# PortaPill_MainBoard.net
KiCad netlist of a schematic drawn in Altium Designer
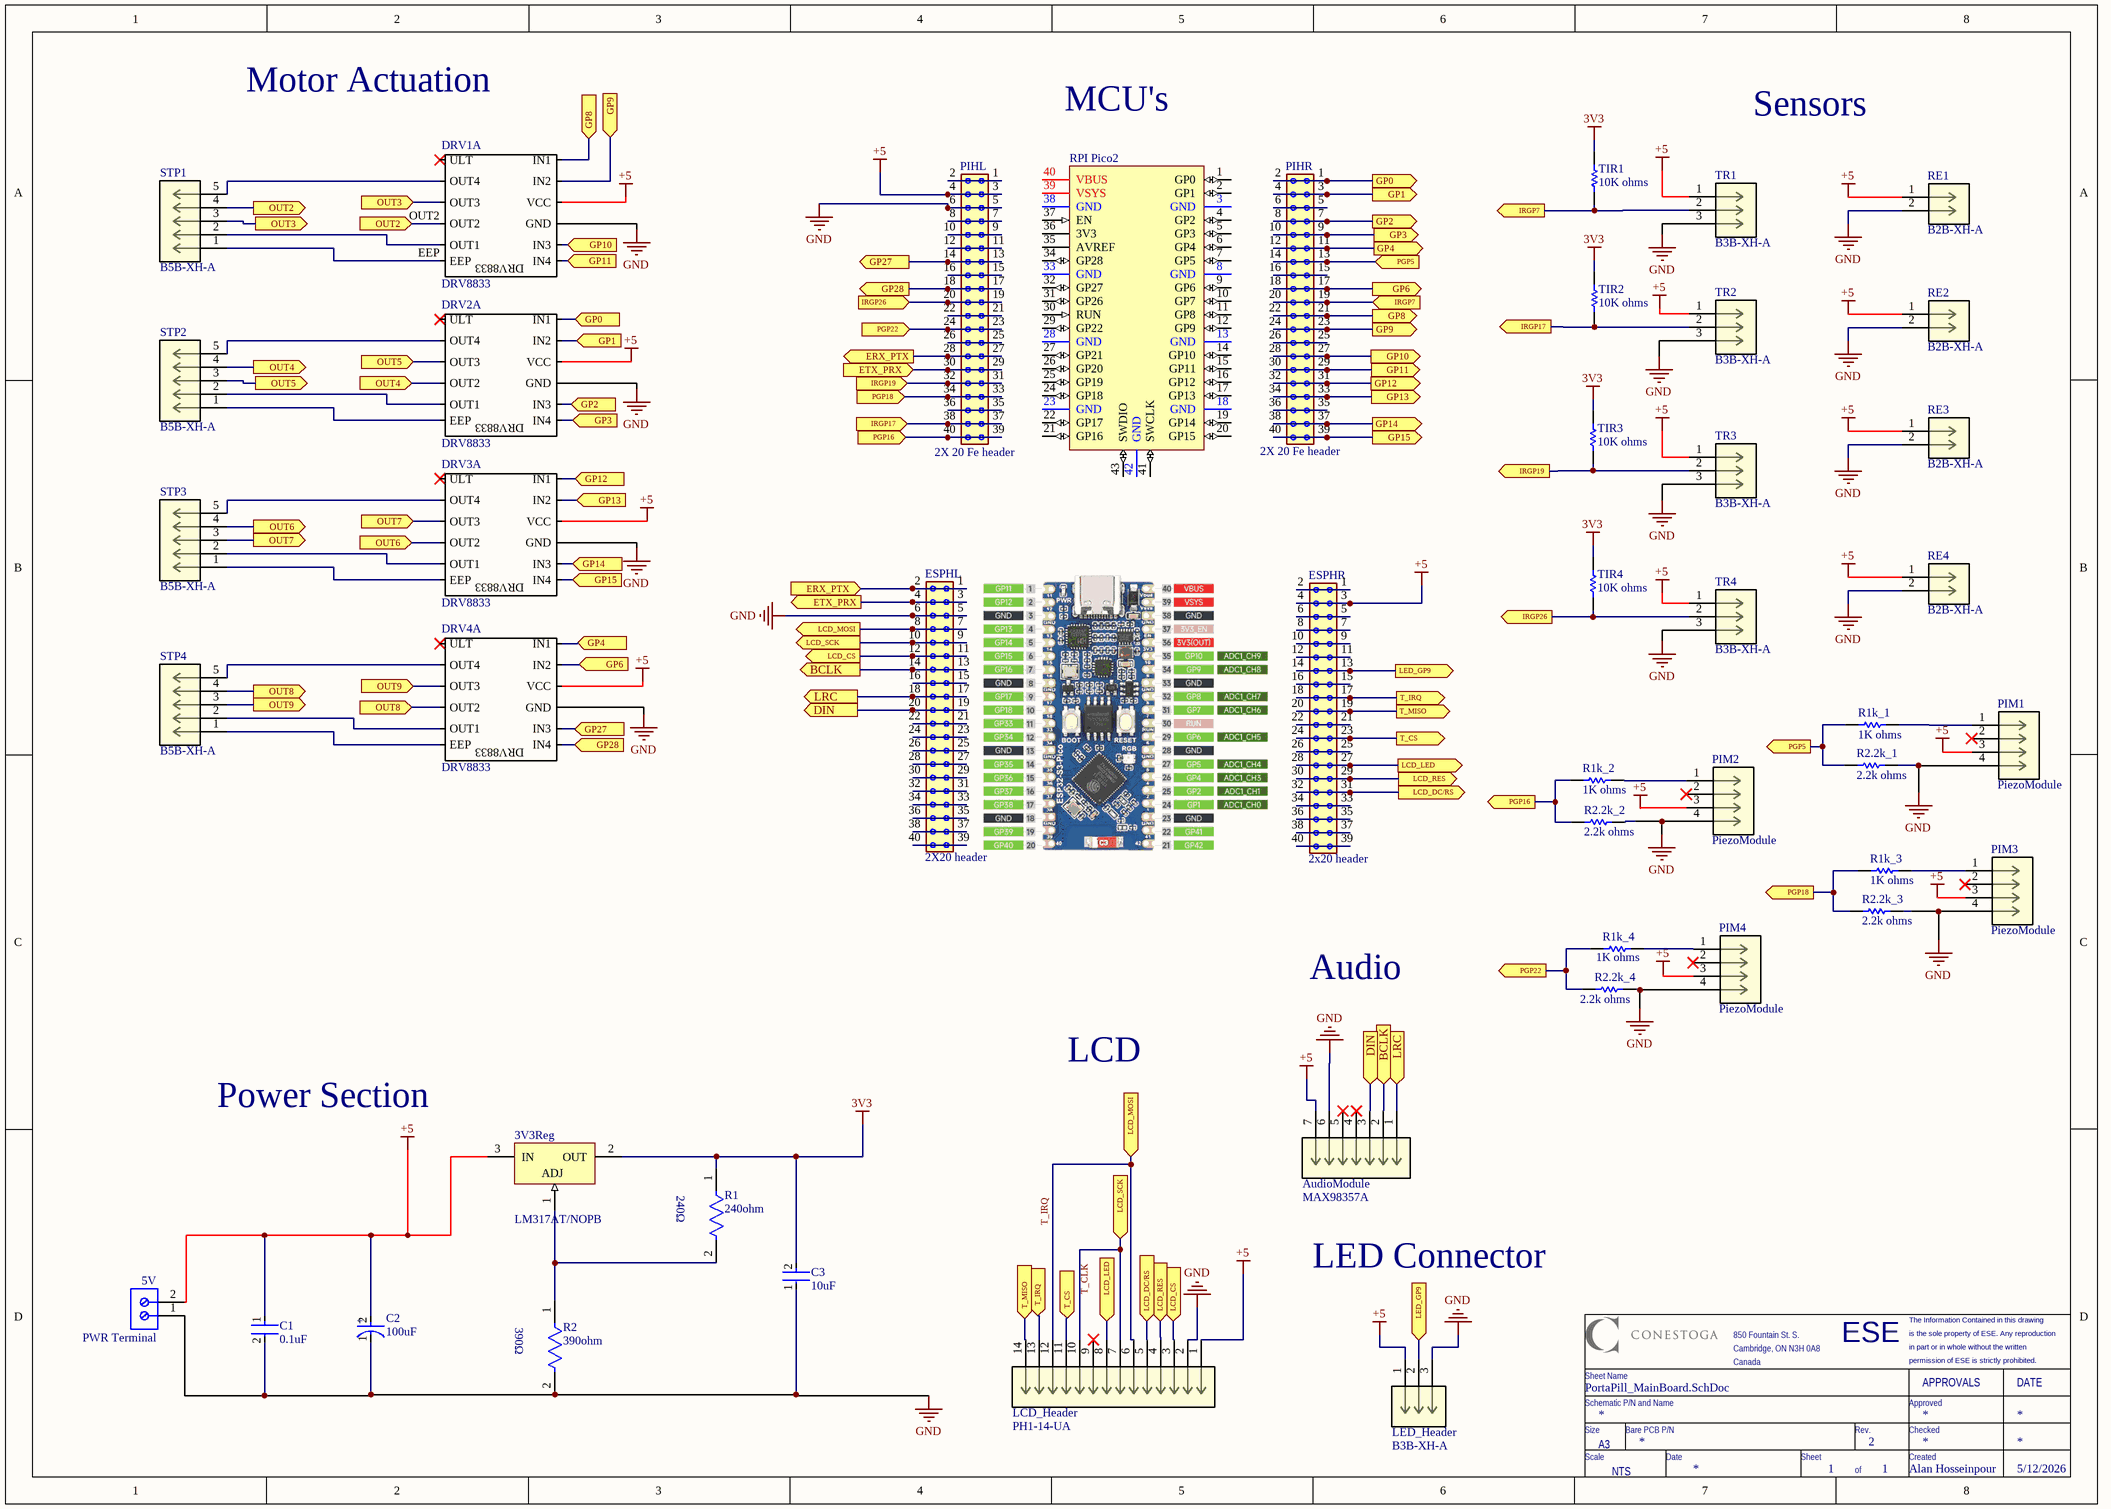
[diagram p0: PortaPill_MainBoard.SchDoc]

(export (version "E")
  (design (tool "Eeschema 10.0.6"))
  (components
    (comp (ref "3V3Reg")
      (value "LM317AT/NOPB")
      (footprint "NDE0003A")
      (description "3-Terminal Adjustable Regulator, 3-pin TO-220, Pb-Free")
      (fields (field (name "MANUFACTURER") "Texas Instruments"))
      (libsource (lib "Altium Content Vault") (part "PM-REG-LM1086ADJ-SIL3"))
    )
    (comp (ref "AudioModule")
      (value "MAX98357A")
      (footprint "CONN07_901471107_MOL")
      (description "C-Grid III PC Board Connector, Single Row, Vertical, 7 Circuits, Tin (Sn) Plating")
      (fields
        (field (name "MANUFACTURER_PART_NUMBER") "901471107")
        (field (name "COPYRIGHT") "Copyright (C) 2026 Ultra Librarian. All rights reserved.")
      )
      (libsource (lib "901471107") (part "901471107"))
    )
    (comp (ref "C1")
      (value "0.1uF")
      (footprint "FP-C410C104M5U5TA7200-MFG")
      (description "C410C104M5U5TA7200\r\nCAP CER 0.1UF 50V Z5U AXIAL")
      (fields (field (name "TOLERANCE") "20%"))
      (libsource (lib "Altium Content Vault") (part "b4654b650e69147ec39a6b967a45e02"))
    )
    (comp (ref "C2")
      (value "100uF")
      (footprint "FP-RAD-TH-D_12_5_0_5-L_25-MFG")
      (description "Aluminum Electrolytic Capacitors (Radial Lead Type) 100uF ±20% 160V\r\nEEUED2C101")
      (fields (field (name "VOLTAGE") "160V") (field (name "TOLERANCE") "20%"))
      (libsource (lib "Altium Content Vault") (part "203bc49f2ac43e59fd269a8c329ed05"))
    )
    (comp (ref "C3")
      (value "10uF")
      (footprint "FP-DE2_D15_T5_F7_5_d0_6-0-MFG")
      (description "Cap Ceramic Disc 10000pF 20% 250VAC Thru-Hole 15.0x5.0x7.5 Bulk\r\n\r\nDE2E3SA103MJ3BT02F")
      (libsource (lib "Altium Content Vault") (part "236180d848d6139a670b325ea6854c9"))
    )
    (comp (ref "DRV1")
      (value "DRV8833")
      (footprint "DRV8833")
      (description "Motor Driver")
      (libsource (lib "") (part "DRV8833_1"))
    )
    (comp (ref "DRV2")
      (value "DRV8833")
      (footprint "DRV8833")
      (description "Motor Driver")
      (libsource (lib "Capstone I library") (part "DRV8833"))
    )
    (comp (ref "DRV3")
      (value "DRV8833")
      (footprint "DRV8833")
      (description "Motor Driver")
      (libsource (lib "Capstone I library") (part "DRV8833"))
    )
    (comp (ref "DRV4")
      (value "DRV8833")
      (footprint "DRV8833")
      (description "Motor Driver")
      (libsource (lib "Capstone I library") (part "DRV8833"))
    )
    (comp (ref "ESPHL")
      (value "2X20 header")
      (footprint "61304021821")
      (description "40 Position Receptacle Connector 0.100 (2.54mm) Through Hole Gold")
      (fields (field (name "MF") "WÃ¼rth Elektronik") (field (name "MP") "61304021821"))
      (libsource (lib "6130XX21821_61304021821") (part "6130XX21821_61304021821"))
    )
    (comp (ref "ESPHR")
      (value "2x20 header")
      (footprint "61304021821")
      (description "40 Position Receptacle Connector 0.100 (2.54mm) Through Hole Gold")
      (fields (field (name "MF") "WÃ¼rth Elektronik") (field (name "MP") "61304021821"))
      (libsource (lib "6130XX21821_61304021821") (part "6130XX21821_61304021821"))
    )
    (comp (ref "LCD_Header")
      (value "PH1-14-UA")
      (footprint "CONN_PH1-14-UA_ADM")
      (description "Description")
      (fields (field (name "COPYRIGHT") "Copyright (C) 2025 Ultra Librarian. All rights reserved."))
      (libsource (lib "PH1-14-UA") (part "PH1-14-UA"))
    )
    (comp (ref "LED_Header")
      (value "B3B-XH-A")
      (footprint "CONN_B3B-XH-A_JST")
      (description "Description")
      (fields (field (name "COPYRIGHT") "Copyright (C) 2026 Ultra Librarian. All rights reserved."))
      (libsource (lib "") (part "B3B-XH-A_1"))
    )
    (comp (ref "PIHL")
      (value "2X 20 Fe header")
      (footprint "61304021821")
      (description "40 Position Receptacle Connector 0.100 (2.54mm) Through Hole Gold")
      (fields (field (name "MF") "WÃ¼rth Elektronik") (field (name "MP") "61304021821"))
      (libsource (lib "6130XX21821_61304021821") (part "6130XX21821_61304021821"))
    )
    (comp (ref "PIHR")
      (value "2X 20 Fe header")
      (footprint "61304021821")
      (description "40 Position Receptacle Connector 0.100 (2.54mm) Through Hole Gold")
      (fields (field (name "MF") "WÃ¼rth Elektronik") (field (name "MP") "61304021821"))
      (libsource (lib "6130XX21821_61304021821") (part "6130XX21821_61304021821"))
    )
    (comp (ref "PIM1")
      (value "PiezoModule")
      (footprint "CONN_PPTC041LFBN-RC_SUL")
      (description "Description")
      (fields
        (field (name "MANUFACTURER_PART_NUMBER") "PPTC041LFBN-RC")
        (field (name "COPYRIGHT") "Copyright (C) 2026 Ultra Librarian. All rights reserved.")
      )
      (libsource (lib "PPTC041LFBN-RC") (part "PPTC041LFBN-RC"))
    )
    (comp (ref "PIM2")
      (value "PiezoModule")
      (footprint "CONN_PPTC041LFBN-RC_SUL")
      (description "Description")
      (fields
        (field (name "MANUFACTURER_PART_NUMBER") "PPTC041LFBN-RC")
        (field (name "COPYRIGHT") "Copyright (C) 2026 Ultra Librarian. All rights reserved.")
      )
      (libsource (lib "PPTC041LFBN-RC") (part "PPTC041LFBN-RC"))
    )
    (comp (ref "PIM3")
      (value "PiezoModule")
      (footprint "CONN_PPTC041LFBN-RC_SUL")
      (description "Description")
      (fields
        (field (name "MANUFACTURER_PART_NUMBER") "PPTC041LFBN-RC")
        (field (name "COPYRIGHT") "Copyright (C) 2026 Ultra Librarian. All rights reserved.")
      )
      (libsource (lib "PPTC041LFBN-RC") (part "PPTC041LFBN-RC"))
    )
    (comp (ref "PIM4")
      (value "PiezoModule")
      (footprint "CONN_PPTC041LFBN-RC_SUL")
      (description "Description")
      (fields
        (field (name "MANUFACTURER_PART_NUMBER") "PPTC041LFBN-RC")
        (field (name "COPYRIGHT") "Copyright (C) 2026 Ultra Librarian. All rights reserved.")
      )
      (libsource (lib "PPTC041LFBN-RC") (part "PPTC041LFBN-RC"))
    )
    (comp (ref "PWR Terminal")
      (value "5V")
      (footprint "691216400002")
      (description "Terminal Block, Wtb, 2Way, 30-12Awg Rohs Compliant: Yes")
      (libsource (lib "Altium Content Vault") (part "TBL - 1R - 02P - Screw"))
    )
    (comp (ref "R1")
      (value "240ohm")
      (footprint "RR02_MFG")
      (description "Fixed Resistor, Metal Film, 2W, 240ohm, 500V, 5% +/-Tol, 300ppm/Cel, Through Hole Mount")
      (fields (field (name "TOLERANCE") "5%"))
      (libsource (lib "Altium Content Vault") (part "beb0a2e81d78bb8429d162089e89c6a"))
    )
    (comp (ref "R1k_1")
      (value "1K ohms")
      (footprint "RESA60-630X240")
      (description "Axial Resistor, 1 KOhm, +/- 1%, 250 mW, -55 to 155 degC, 2-Pin THD, RoHS, Bulk")
      (fields (field (name "TOLERANCE") "1%"))
      (libsource (lib "Altium Content Vault") (part "RES-2"))
    )
    (comp (ref "R1k_2")
      (value "1K ohms")
      (footprint "RESA60-630X240")
      (description "Axial Resistor, 1 KOhm, +/- 1%, 250 mW, -55 to 155 degC, 2-Pin THD, RoHS, Bulk")
      (fields (field (name "TOLERANCE") "1%"))
      (libsource (lib "Altium Content Vault") (part "RES-2"))
    )
    (comp (ref "R1k_3")
      (value "1K ohms")
      (footprint "RESA60-630X240")
      (description "Axial Resistor, 1 KOhm, +/- 1%, 250 mW, -55 to 155 degC, 2-Pin THD, RoHS, Bulk")
      (fields (field (name "TOLERANCE") "1%"))
      (libsource (lib "Altium Content Vault") (part "RES-2"))
    )
    (comp (ref "R1k_4")
      (value "1K ohms")
      (footprint "RESA60-630X240")
      (description "Axial Resistor, 1 KOhm, +/- 1%, 250 mW, -55 to 155 degC, 2-Pin THD, RoHS, Bulk")
      (fields (field (name "TOLERANCE") "1%"))
      (libsource (lib "Altium Content Vault") (part "RES-2"))
    )
    (comp (ref "R2")
      (value "390ohm")
      (footprint "RR02_MFG")
      (description "Fixed Resistor, Metal Film, 2W, 240ohm, 500V, 5% +/-Tol, 300ppm/Cel, Through Hole Mount")
      (fields (field (name "TOLERANCE") "5%"))
      (libsource (lib "Altium Content Vault") (part "beb0a2e81d78bb8429d162089e89c6a"))
    )
    (comp (ref "R2.2k_1")
      (value "2.2k ohms")
      (footprint "RESA60-630X240")
      (description "Axial Resistor, 1 KOhm, +/- 1%, 250 mW, -55 to 155 degC, 2-Pin THD, RoHS, Bulk")
      (fields (field (name "TOLERANCE") "1%"))
      (libsource (lib "Altium Content Vault") (part "RES-2"))
    )
    (comp (ref "R2.2k_2")
      (value "2.2k ohms")
      (footprint "RESA60-630X240")
      (description "Axial Resistor, 1 KOhm, +/- 1%, 250 mW, -55 to 155 degC, 2-Pin THD, RoHS, Bulk")
      (fields (field (name "TOLERANCE") "1%"))
      (libsource (lib "Altium Content Vault") (part "RES-2"))
    )
    (comp (ref "R2.2k_3")
      (value "2.2k ohms")
      (footprint "RESA60-630X240")
      (description "Axial Resistor, 1 KOhm, +/- 1%, 250 mW, -55 to 155 degC, 2-Pin THD, RoHS, Bulk")
      (fields (field (name "TOLERANCE") "1%"))
      (libsource (lib "Altium Content Vault") (part "RES-2"))
    )
    (comp (ref "R2.2k_4")
      (value "2.2k ohms")
      (footprint "RESA60-630X240")
      (description "Axial Resistor, 1 KOhm, +/- 1%, 250 mW, -55 to 155 degC, 2-Pin THD, RoHS, Bulk")
      (fields (field (name "TOLERANCE") "1%"))
      (libsource (lib "Altium Content Vault") (part "RES-2"))
    )
    (comp (ref "RE1")
      (value "B2B-XH-A")
      (footprint "CONN_B2B-XH-A_JST")
      (description "Description")
      (fields (field (name "COPYRIGHT") "Copyright (C) 2026 Ultra Librarian. All rights reserved."))
      (libsource (lib "B2B-XH-A") (part "B2B-XH-A"))
    )
    (comp (ref "RE2")
      (value "B2B-XH-A")
      (footprint "CONN_B2B-XH-A_JST")
      (description "Description")
      (fields (field (name "COPYRIGHT") "Copyright (C) 2026 Ultra Librarian. All rights reserved."))
      (libsource (lib "B2B-XH-A") (part "B2B-XH-A"))
    )
    (comp (ref "RE3")
      (value "B2B-XH-A")
      (footprint "CONN_B2B-XH-A_JST")
      (description "Description")
      (fields (field (name "COPYRIGHT") "Copyright (C) 2026 Ultra Librarian. All rights reserved."))
      (libsource (lib "B2B-XH-A") (part "B2B-XH-A"))
    )
    (comp (ref "RE4")
      (value "B2B-XH-A")
      (footprint "CONN_B2B-XH-A_JST")
      (description "Description")
      (fields (field (name "COPYRIGHT") "Copyright (C) 2026 Ultra Librarian. All rights reserved."))
      (libsource (lib "B2B-XH-A") (part "B2B-XH-A"))
    )
    (comp (ref "RPI Pico2")
      (value "RPI-PICO-MOD_SM")
      (footprint "AG.Modules:RPI-PICO-MOD")
      (description "RASPBERRY PI PICO RP2040 BOARD NO TEST PADS")
      (fields
        (field (name "MANUFACTURER") "Raspberry Pi Foundation")
        (field (name "MANUFACTURER PART NO") "SC0915")
      )
      (libsource (lib "RPi_Pico") (part "RPI-PICO-MOD_SM"))
    )
    (comp (ref "STP1")
      (value "B5B-XH-A")
      (footprint "CONN_B5B-XH-A_JST")
      (description "Description")
      (fields (field (name "COPYRIGHT") "Copyright (C) 2026 Ultra Librarian. All rights reserved."))
      (libsource (lib "B5B-XH-A") (part "B5B-XH-A"))
    )
    (comp (ref "STP2")
      (value "B5B-XH-A")
      (footprint "CONN_B5B-XH-A_JST")
      (description "Description")
      (fields (field (name "COPYRIGHT") "Copyright (C) 2026 Ultra Librarian. All rights reserved."))
      (libsource (lib "B5B-XH-A") (part "B5B-XH-A"))
    )
    (comp (ref "STP3")
      (value "B5B-XH-A")
      (footprint "CONN_B5B-XH-A_JST")
      (description "Description")
      (fields (field (name "COPYRIGHT") "Copyright (C) 2026 Ultra Librarian. All rights reserved."))
      (libsource (lib "B5B-XH-A") (part "B5B-XH-A"))
    )
    (comp (ref "STP4")
      (value "B5B-XH-A")
      (footprint "CONN_B5B-XH-A_JST")
      (description "Description")
      (fields (field (name "COPYRIGHT") "Copyright (C) 2026 Ultra Librarian. All rights reserved."))
      (libsource (lib "B5B-XH-A") (part "B5B-XH-A"))
    )
    (comp (ref "TIR1")
      (value "10K ohms")
      (footprint "RESA60-630X240")
      (description "Axial Resistor, 1 KOhm, +/- 1%, 250 mW, -55 to 155 degC, 2-Pin THD, RoHS, Bulk")
      (fields (field (name "TOLERANCE") "1%"))
      (libsource (lib "Altium Content Vault") (part "RES-2"))
    )
    (comp (ref "TIR2")
      (value "10K ohms")
      (footprint "RESA60-630X240")
      (description "Axial Resistor, 1 KOhm, +/- 1%, 250 mW, -55 to 155 degC, 2-Pin THD, RoHS, Bulk")
      (fields (field (name "TOLERANCE") "1%"))
      (libsource (lib "Altium Content Vault") (part "RES-2"))
    )
    (comp (ref "TIR3")
      (value "10K ohms")
      (footprint "RESA60-630X240")
      (description "Axial Resistor, 1 KOhm, +/- 1%, 250 mW, -55 to 155 degC, 2-Pin THD, RoHS, Bulk")
      (fields (field (name "TOLERANCE") "1%"))
      (libsource (lib "Altium Content Vault") (part "RES-2"))
    )
    (comp (ref "TIR4")
      (value "10K ohms")
      (footprint "RESA60-630X240")
      (description "Axial Resistor, 1 KOhm, +/- 1%, 250 mW, -55 to 155 degC, 2-Pin THD, RoHS, Bulk")
      (fields (field (name "TOLERANCE") "1%"))
      (libsource (lib "Altium Content Vault") (part "RES-2"))
    )
    (comp (ref "TR1")
      (value "B3B-XH-A")
      (footprint "CONN_B3B-XH-A_JST")
      (description "Description")
      (fields (field (name "COPYRIGHT") "Copyright (C) 2026 Ultra Librarian. All rights reserved."))
      (libsource (lib "B3B-XH-A") (part "B3B-XH-A"))
    )
    (comp (ref "TR2")
      (value "B3B-XH-A")
      (footprint "CONN_B3B-XH-A_JST")
      (description "Description")
      (fields (field (name "COPYRIGHT") "Copyright (C) 2026 Ultra Librarian. All rights reserved."))
      (libsource (lib "B3B-XH-A") (part "B3B-XH-A"))
    )
    (comp (ref "TR3")
      (value "B3B-XH-A")
      (footprint "CONN_B3B-XH-A_JST")
      (description "Description")
      (fields (field (name "COPYRIGHT") "Copyright (C) 2026 Ultra Librarian. All rights reserved."))
      (libsource (lib "B3B-XH-A") (part "B3B-XH-A"))
    )
    (comp (ref "TR4")
      (value "B3B-XH-A")
      (footprint "CONN_B3B-XH-A_JST")
      (description "Description")
      (fields (field (name "COPYRIGHT") "Copyright (C) 2026 Ultra Librarian. All rights reserved."))
      (libsource (lib "B3B-XH-A") (part "B3B-XH-A"))
    )
  )
  (nets
    (net (code "1") (name "+5") (class "Default")
      (node (ref "3V3Reg") (pin "3") (pinfunction "IN_3") (pintype "power_in"))
      (node (ref "AudioModule") (pin "7") (pinfunction "7_7") (pintype "passive"))
      (node (ref "C1") (pin "1") (pinfunction "1_1") (pintype "passive"))
      (node (ref "C2") (pin "2") (pinfunction "A_2") (pintype "passive"))
      (node (ref "DRV1") (pin "VCC") (pinfunction "VCC_VCC") (pintype "passive"))
      (node (ref "DRV2") (pin "VCC") (pinfunction "VCC_VCC") (pintype "passive"))
      (node (ref "DRV3") (pin "VCC") (pinfunction "VCC_VCC") (pintype "passive"))
      (node (ref "DRV4") (pin "VCC") (pinfunction "VCC_VCC") (pintype "passive"))
      (node (ref "ESPHR") (pin "3") (pinfunction "3_3") (pintype "passive"))
      (node (ref "ESPHR") (pin "4") (pinfunction "4_4") (pintype "passive"))
      (node (ref "LCD_Header") (pin "1") (pinfunction "1_1") (pintype "passive"))
      (node (ref "LED_Header") (pin "1") (pinfunction "1_1") (pintype "passive"))
      (node (ref "PIHL") (pin "3") (pinfunction "3_3") (pintype "passive"))
      (node (ref "PIHL") (pin "4") (pinfunction "4_4") (pintype "passive"))
      (node (ref "PIM1") (pin "3") (pinfunction "3_3") (pintype "passive"))
      (node (ref "PIM2") (pin "3") (pinfunction "3_3") (pintype "passive"))
      (node (ref "PIM3") (pin "3") (pinfunction "3_3") (pintype "passive"))
      (node (ref "PIM4") (pin "3") (pinfunction "3_3") (pintype "passive"))
      (node (ref "PWR Terminal") (pin "2") (pinfunction "2_2") (pintype "passive"))
      (node (ref "RE1") (pin "1") (pinfunction "1_1") (pintype "passive"))
      (node (ref "RE2") (pin "1") (pinfunction "1_1") (pintype "passive"))
      (node (ref "RE3") (pin "1") (pinfunction "1_1") (pintype "passive"))
      (node (ref "RE4") (pin "1") (pinfunction "1_1") (pintype "passive"))
      (node (ref "TR1") (pin "1") (pinfunction "1_1") (pintype "passive"))
      (node (ref "TR2") (pin "1") (pinfunction "1_1") (pintype "passive"))
      (node (ref "TR3") (pin "1") (pinfunction "1_1") (pintype "passive"))
      (node (ref "TR4") (pin "1") (pinfunction "1_1") (pintype "passive"))
    )
    (net (code "2") (name "/BCLK") (class "Default")
      (node (ref "AudioModule") (pin "2") (pinfunction "2_2") (pintype "passive"))
      (node (ref "ESPHL") (pin "13") (pinfunction "13_13") (pintype "passive"))
      (node (ref "ESPHL") (pin "14") (pinfunction "14_14") (pintype "passive"))
    )
    (net (code "3") (name "/DIN") (class "Default")
      (node (ref "AudioModule") (pin "3") (pinfunction "3_3") (pintype "passive"))
      (node (ref "ESPHL") (pin "19") (pinfunction "19_19") (pintype "passive"))
      (node (ref "ESPHL") (pin "20") (pinfunction "20_20") (pintype "passive"))
    )
    (net (code "4") (name "/ERX_PTX") (class "Default")
      (node (ref "ESPHL") (pin "1") (pinfunction "1_1") (pintype "passive"))
      (node (ref "ESPHL") (pin "2") (pinfunction "2_2") (pintype "passive"))
      (node (ref "PIHL") (pin "27") (pinfunction "27_27") (pintype "passive"))
      (node (ref "PIHL") (pin "28") (pinfunction "28_28") (pintype "passive"))
    )
    (net (code "5") (name "/ETX_PRX") (class "Default")
      (node (ref "ESPHL") (pin "3") (pinfunction "3_3") (pintype "passive"))
      (node (ref "ESPHL") (pin "4") (pinfunction "4_4") (pintype "passive"))
      (node (ref "PIHL") (pin "29") (pinfunction "29_29") (pintype "passive"))
      (node (ref "PIHL") (pin "30") (pinfunction "30_30") (pintype "passive"))
    )
    (net (code "6") (name "/GP0") (class "Default")
      (node (ref "DRV2") (pin "IN1") (pinfunction "IN1_IN1") (pintype "passive"))
      (node (ref "PIHR") (pin "1") (pinfunction "1_1") (pintype "passive"))
      (node (ref "PIHR") (pin "2") (pinfunction "2_2") (pintype "passive"))
    )
    (net (code "7") (name "/GP1") (class "Default")
      (node (ref "DRV2") (pin "IN2") (pinfunction "IN2_IN2") (pintype "passive"))
      (node (ref "PIHR") (pin "3") (pinfunction "3_3") (pintype "passive"))
      (node (ref "PIHR") (pin "4") (pinfunction "4_4") (pintype "passive"))
    )
    (net (code "8") (name "/GP2") (class "Default")
      (node (ref "DRV2") (pin "IN3") (pinfunction "IN3_IN3") (pintype "passive"))
      (node (ref "PIHR") (pin "7") (pinfunction "7_7") (pintype "passive"))
      (node (ref "PIHR") (pin "8") (pinfunction "8_8") (pintype "passive"))
    )
    (net (code "9") (name "/GP3") (class "Default")
      (node (ref "DRV2") (pin "IN4") (pinfunction "IN4_IN4") (pintype "passive"))
      (node (ref "PIHR") (pin "10") (pinfunction "10_10") (pintype "passive"))
      (node (ref "PIHR") (pin "9") (pinfunction "9_9") (pintype "passive"))
    )
    (net (code "10") (name "/GP4") (class "Default")
      (node (ref "DRV4") (pin "IN1") (pinfunction "IN1_IN1") (pintype "passive"))
      (node (ref "PIHR") (pin "11") (pinfunction "11_11") (pintype "passive"))
      (node (ref "PIHR") (pin "12") (pinfunction "12_12") (pintype "passive"))
    )
    (net (code "11") (name "/GP6") (class "Default")
      (node (ref "DRV4") (pin "IN2") (pinfunction "IN2_IN2") (pintype "passive"))
      (node (ref "PIHR") (pin "17") (pinfunction "17_17") (pintype "passive"))
      (node (ref "PIHR") (pin "18") (pinfunction "18_18") (pintype "passive"))
    )
    (net (code "12") (name "/GP8") (class "Default")
      (node (ref "DRV1") (pin "IN1") (pinfunction "IN1_IN1") (pintype "passive"))
      (node (ref "PIHR") (pin "21") (pinfunction "21_21") (pintype "passive"))
      (node (ref "PIHR") (pin "22") (pinfunction "22_22") (pintype "passive"))
    )
    (net (code "13") (name "/GP9") (class "Default")
      (node (ref "DRV1") (pin "IN2") (pinfunction "IN2_IN2") (pintype "passive"))
      (node (ref "PIHR") (pin "23") (pinfunction "23_23") (pintype "passive"))
      (node (ref "PIHR") (pin "24") (pinfunction "24_24") (pintype "passive"))
    )
    (net (code "14") (name "/GP10") (class "Default")
      (node (ref "DRV1") (pin "IN3") (pinfunction "IN3_IN3") (pintype "passive"))
      (node (ref "PIHR") (pin "27") (pinfunction "27_27") (pintype "passive"))
      (node (ref "PIHR") (pin "28") (pinfunction "28_28") (pintype "passive"))
    )
    (net (code "15") (name "/GP11") (class "Default")
      (node (ref "DRV1") (pin "IN4") (pinfunction "IN4_IN4") (pintype "passive"))
      (node (ref "PIHR") (pin "29") (pinfunction "29_29") (pintype "passive"))
      (node (ref "PIHR") (pin "30") (pinfunction "30_30") (pintype "passive"))
    )
    (net (code "16") (name "/GP12") (class "Default")
      (node (ref "DRV3") (pin "IN1") (pinfunction "IN1_IN1") (pintype "passive"))
      (node (ref "PIHR") (pin "31") (pinfunction "31_31") (pintype "passive"))
      (node (ref "PIHR") (pin "32") (pinfunction "32_32") (pintype "passive"))
    )
    (net (code "17") (name "/GP13") (class "Default")
      (node (ref "DRV3") (pin "IN2") (pinfunction "IN2_IN2") (pintype "passive"))
      (node (ref "PIHR") (pin "33") (pinfunction "33_33") (pintype "passive"))
      (node (ref "PIHR") (pin "34") (pinfunction "34_34") (pintype "passive"))
    )
    (net (code "18") (name "/GP14") (class "Default")
      (node (ref "DRV3") (pin "IN3") (pinfunction "IN3_IN3") (pintype "passive"))
      (node (ref "PIHR") (pin "37") (pinfunction "37_37") (pintype "passive"))
      (node (ref "PIHR") (pin "38") (pinfunction "38_38") (pintype "passive"))
    )
    (net (code "19") (name "/GP15") (class "Default")
      (node (ref "DRV3") (pin "IN4") (pinfunction "IN4_IN4") (pintype "passive"))
      (node (ref "PIHR") (pin "39") (pinfunction "39_39") (pintype "passive"))
      (node (ref "PIHR") (pin "40") (pinfunction "40_40") (pintype "passive"))
    )
    (net (code "20") (name "/GP27") (class "Default")
      (node (ref "DRV4") (pin "IN3") (pinfunction "IN3_IN3") (pintype "passive"))
      (node (ref "PIHL") (pin "13") (pinfunction "13_13") (pintype "passive"))
      (node (ref "PIHL") (pin "14") (pinfunction "14_14") (pintype "passive"))
    )
    (net (code "21") (name "/GP28") (class "Default")
      (node (ref "DRV4") (pin "IN4") (pinfunction "IN4_IN4") (pintype "passive"))
      (node (ref "PIHL") (pin "17") (pinfunction "17_17") (pintype "passive"))
      (node (ref "PIHL") (pin "18") (pinfunction "18_18") (pintype "passive"))
    )
    (net (code "22") (name "/IRGP7") (class "Default")
      (node (ref "PIHR") (pin "19") (pinfunction "19_19") (pintype "passive"))
      (node (ref "PIHR") (pin "20") (pinfunction "20_20") (pintype "passive"))
      (node (ref "TIR1") (pin "1") (pinfunction "1_1") (pintype "passive"))
      (node (ref "TR1") (pin "2") (pinfunction "2_2") (pintype "passive"))
    )
    (net (code "23") (name "/IRGP17") (class "Default")
      (node (ref "PIHL") (pin "37") (pinfunction "37_37") (pintype "passive"))
      (node (ref "PIHL") (pin "38") (pinfunction "38_38") (pintype "passive"))
      (node (ref "TIR2") (pin "1") (pinfunction "1_1") (pintype "passive"))
      (node (ref "TR2") (pin "2") (pinfunction "2_2") (pintype "passive"))
    )
    (net (code "24") (name "/IRGP19") (class "Default")
      (node (ref "PIHL") (pin "31") (pinfunction "31_31") (pintype "passive"))
      (node (ref "PIHL") (pin "32") (pinfunction "32_32") (pintype "passive"))
      (node (ref "TIR3") (pin "1") (pinfunction "1_1") (pintype "passive"))
      (node (ref "TR3") (pin "2") (pinfunction "2_2") (pintype "passive"))
    )
    (net (code "25") (name "/IRGP26") (class "Default")
      (node (ref "PIHL") (pin "19") (pinfunction "19_19") (pintype "passive"))
      (node (ref "PIHL") (pin "20") (pinfunction "20_20") (pintype "passive"))
      (node (ref "TIR4") (pin "1") (pinfunction "1_1") (pintype "passive"))
      (node (ref "TR4") (pin "2") (pinfunction "2_2") (pintype "passive"))
    )
    (net (code "26") (name "/LCD_CS") (class "Default")
      (node (ref "ESPHL") (pin "11") (pinfunction "11_11") (pintype "passive"))
      (node (ref "ESPHL") (pin "12") (pinfunction "12_12") (pintype "passive"))
      (node (ref "LCD_Header") (pin "3") (pinfunction "3_3") (pintype "passive"))
    )
    (net (code "27") (name "/LCD_DC{slash}RS") (class "Default")
      (node (ref "ESPHR") (pin "31") (pinfunction "31_31") (pintype "passive"))
      (node (ref "ESPHR") (pin "32") (pinfunction "32_32") (pintype "passive"))
      (node (ref "LCD_Header") (pin "5") (pinfunction "5_5") (pintype "passive"))
    )
    (net (code "28") (name "/LCD_LED") (class "Default")
      (node (ref "ESPHR") (pin "27") (pinfunction "27_27") (pintype "passive"))
      (node (ref "ESPHR") (pin "28") (pinfunction "28_28") (pintype "passive"))
      (node (ref "LCD_Header") (pin "8") (pinfunction "8_8") (pintype "passive"))
    )
    (net (code "29") (name "/LCD_MOSI") (class "Default")
      (node (ref "ESPHL") (pin "7") (pinfunction "7_7") (pintype "passive"))
      (node (ref "ESPHL") (pin "8") (pinfunction "8_8") (pintype "passive"))
      (node (ref "LCD_Header") (pin "12") (pinfunction "12_12") (pintype "passive"))
      (node (ref "LCD_Header") (pin "6") (pinfunction "6_6") (pintype "passive"))
    )
    (net (code "30") (name "/LCD_RES") (class "Default")
      (node (ref "ESPHR") (pin "29") (pinfunction "29_29") (pintype "passive"))
      (node (ref "ESPHR") (pin "30") (pinfunction "30_30") (pintype "passive"))
      (node (ref "LCD_Header") (pin "4") (pinfunction "4_4") (pintype "passive"))
    )
    (net (code "31") (name "/LCD_SCK") (class "Default")
      (node (ref "ESPHL") (pin "10") (pinfunction "10_10") (pintype "passive"))
      (node (ref "ESPHL") (pin "9") (pinfunction "9_9") (pintype "passive"))
      (node (ref "LCD_Header") (pin "10") (pinfunction "10_10") (pintype "passive"))
      (node (ref "LCD_Header") (pin "7") (pinfunction "7_7") (pintype "passive"))
    )
    (net (code "32") (name "/LED_GP9") (class "Default")
      (node (ref "ESPHR") (pin "13") (pinfunction "13_13") (pintype "passive"))
      (node (ref "ESPHR") (pin "14") (pinfunction "14_14") (pintype "passive"))
      (node (ref "LED_Header") (pin "2") (pinfunction "2_2") (pintype "passive"))
    )
    (net (code "33") (name "/LRC") (class "Default")
      (node (ref "AudioModule") (pin "1") (pinfunction "1_1") (pintype "passive"))
      (node (ref "ESPHL") (pin "17") (pinfunction "17_17") (pintype "passive"))
      (node (ref "ESPHL") (pin "18") (pinfunction "18_18") (pintype "passive"))
    )
    (net (code "34") (name "/OUT2") (class "Default")
      (node (ref "DRV1") (pin "OUT2") (pinfunction "OUT2_OUT2") (pintype "passive"))
      (node (ref "STP1") (pin "4") (pinfunction "4_4") (pintype "passive"))
    )
    (net (code "35") (name "/OUT3") (class "Default")
      (node (ref "DRV1") (pin "OUT3") (pinfunction "OUT3_OUT3") (pintype "passive"))
      (node (ref "STP1") (pin "3") (pinfunction "3_3") (pintype "passive"))
    )
    (net (code "36") (name "/OUT4") (class "Default")
      (node (ref "DRV2") (pin "OUT2") (pinfunction "OUT2_OUT2") (pintype "passive"))
      (node (ref "STP2") (pin "4") (pinfunction "4_4") (pintype "passive"))
    )
    (net (code "37") (name "/OUT5") (class "Default")
      (node (ref "DRV2") (pin "OUT3") (pinfunction "OUT3_OUT3") (pintype "passive"))
      (node (ref "STP2") (pin "3") (pinfunction "3_3") (pintype "passive"))
    )
    (net (code "38") (name "/OUT6") (class "Default")
      (node (ref "DRV3") (pin "OUT2") (pinfunction "OUT2_OUT2") (pintype "passive"))
      (node (ref "STP3") (pin "4") (pinfunction "4_4") (pintype "passive"))
    )
    (net (code "39") (name "/OUT7") (class "Default")
      (node (ref "DRV3") (pin "OUT3") (pinfunction "OUT3_OUT3") (pintype "passive"))
      (node (ref "STP3") (pin "3") (pinfunction "3_3") (pintype "passive"))
    )
    (net (code "40") (name "/OUT8") (class "Default")
      (node (ref "DRV4") (pin "OUT2") (pinfunction "OUT2_OUT2") (pintype "passive"))
      (node (ref "STP4") (pin "4") (pinfunction "4_4") (pintype "passive"))
    )
    (net (code "41") (name "/OUT9") (class "Default")
      (node (ref "DRV4") (pin "OUT3") (pinfunction "OUT3_OUT3") (pintype "passive"))
      (node (ref "STP4") (pin "3") (pinfunction "3_3") (pintype "passive"))
    )
    (net (code "42") (name "/PGP5") (class "Default")
      (node (ref "PIHR") (pin "13") (pinfunction "13_13") (pintype "passive"))
      (node (ref "PIHR") (pin "14") (pinfunction "14_14") (pintype "passive"))
      (node (ref "R1k_1") (pin "1") (pinfunction "1_1") (pintype "passive"))
      (node (ref "R2.2k_1") (pin "1") (pinfunction "1_1") (pintype "passive"))
    )
    (net (code "43") (name "/PGP16") (class "Default")
      (node (ref "PIHL") (pin "39") (pinfunction "39_39") (pintype "passive"))
      (node (ref "PIHL") (pin "40") (pinfunction "40_40") (pintype "passive"))
      (node (ref "R1k_2") (pin "1") (pinfunction "1_1") (pintype "passive"))
      (node (ref "R2.2k_2") (pin "1") (pinfunction "1_1") (pintype "passive"))
    )
    (net (code "44") (name "/PGP18") (class "Default")
      (node (ref "PIHL") (pin "33") (pinfunction "33_33") (pintype "passive"))
      (node (ref "PIHL") (pin "34") (pinfunction "34_34") (pintype "passive"))
      (node (ref "R1k_3") (pin "1") (pinfunction "1_1") (pintype "passive"))
      (node (ref "R2.2k_3") (pin "1") (pinfunction "1_1") (pintype "passive"))
    )
    (net (code "45") (name "/PGP22") (class "Default")
      (node (ref "PIHL") (pin "23") (pinfunction "23_23") (pintype "passive"))
      (node (ref "PIHL") (pin "24") (pinfunction "24_24") (pintype "passive"))
      (node (ref "R1k_4") (pin "1") (pinfunction "1_1") (pintype "passive"))
      (node (ref "R2.2k_4") (pin "1") (pinfunction "1_1") (pintype "passive"))
    )
    (net (code "47") (name "/T_CS") (class "Default")
      (node (ref "ESPHR") (pin "23") (pinfunction "23_23") (pintype "passive"))
      (node (ref "ESPHR") (pin "24") (pinfunction "24_24") (pintype "passive"))
      (node (ref "LCD_Header") (pin "11") (pinfunction "11_11") (pintype "passive"))
    )
    (net (code "48") (name "/T_IRQ") (class "Default")
      (node (ref "ESPHR") (pin "17") (pinfunction "17_17") (pintype "passive"))
      (node (ref "ESPHR") (pin "18") (pinfunction "18_18") (pintype "passive"))
      (node (ref "LCD_Header") (pin "13") (pinfunction "13_13") (pintype "passive"))
    )
    (net (code "49") (name "/T_MISO") (class "Default")
      (node (ref "ESPHR") (pin "19") (pinfunction "19_19") (pintype "passive"))
      (node (ref "ESPHR") (pin "20") (pinfunction "20_20") (pintype "passive"))
      (node (ref "LCD_Header") (pin "14") (pinfunction "14_14") (pintype "passive"))
    )
    (net (code "50") (name "3V3") (class "Default")
      (node (ref "3V3Reg") (pin "2") (pinfunction "OUT_2") (pintype "power_in"))
      (node (ref "C3") (pin "2") (pinfunction "2_2") (pintype "passive"))
      (node (ref "R1") (pin "1") (pinfunction "1_1") (pintype "passive"))
      (node (ref "TIR1") (pin "2") (pinfunction "2_2") (pintype "passive"))
      (node (ref "TIR2") (pin "2") (pinfunction "2_2") (pintype "passive"))
      (node (ref "TIR3") (pin "2") (pinfunction "2_2") (pintype "passive"))
      (node (ref "TIR4") (pin "2") (pinfunction "2_2") (pintype "passive"))
    )
    (net (code "51") (name "GND") (class "Default")
      (node (ref "AudioModule") (pin "6") (pinfunction "6_6") (pintype "passive"))
      (node (ref "C1") (pin "2") (pinfunction "2_2") (pintype "passive"))
      (node (ref "C2") (pin "1") (pinfunction "C_1") (pintype "passive"))
      (node (ref "C3") (pin "1") (pinfunction "1_1") (pintype "passive"))
      (node (ref "DRV1") (pin "GND") (pinfunction "GND_GND") (pintype "passive"))
      (node (ref "DRV2") (pin "GND") (pinfunction "GND_GND") (pintype "passive"))
      (node (ref "DRV3") (pin "GND") (pinfunction "GND_GND") (pintype "passive"))
      (node (ref "DRV4") (pin "GND") (pinfunction "GND_GND") (pintype "passive"))
      (node (ref "ESPHL") (pin "5") (pinfunction "5_5") (pintype "passive"))
      (node (ref "ESPHL") (pin "6") (pinfunction "6_6") (pintype "passive"))
      (node (ref "LCD_Header") (pin "2") (pinfunction "2_2") (pintype "passive"))
      (node (ref "LED_Header") (pin "3") (pinfunction "3_3") (pintype "passive"))
      (node (ref "PIHL") (pin "5") (pinfunction "5_5") (pintype "passive"))
      (node (ref "PIHL") (pin "6") (pinfunction "6_6") (pintype "passive"))
      (node (ref "PIM1") (pin "4") (pinfunction "4_4") (pintype "passive"))
      (node (ref "PIM2") (pin "4") (pinfunction "4_4") (pintype "passive"))
      (node (ref "PIM3") (pin "4") (pinfunction "4_4") (pintype "passive"))
      (node (ref "PIM4") (pin "4") (pinfunction "4_4") (pintype "passive"))
      (node (ref "PWR Terminal") (pin "1") (pinfunction "1_1") (pintype "passive"))
      (node (ref "R2") (pin "2") (pinfunction "2_2") (pintype "passive"))
      (node (ref "R2.2k_1") (pin "2") (pinfunction "2_2") (pintype "passive"))
      (node (ref "R2.2k_2") (pin "2") (pinfunction "2_2") (pintype "passive"))
      (node (ref "R2.2k_3") (pin "2") (pinfunction "2_2") (pintype "passive"))
      (node (ref "R2.2k_4") (pin "2") (pinfunction "2_2") (pintype "passive"))
      (node (ref "RE1") (pin "2") (pinfunction "2_2") (pintype "passive"))
      (node (ref "RE2") (pin "2") (pinfunction "2_2") (pintype "passive"))
      (node (ref "RE3") (pin "2") (pinfunction "2_2") (pintype "passive"))
      (node (ref "RE4") (pin "2") (pinfunction "2_2") (pintype "passive"))
      (node (ref "TR1") (pin "3") (pinfunction "3_3") (pintype "passive"))
      (node (ref "TR2") (pin "3") (pinfunction "3_3") (pintype "passive"))
      (node (ref "TR3") (pin "3") (pinfunction "3_3") (pintype "passive"))
      (node (ref "TR4") (pin "3") (pinfunction "3_3") (pintype "passive"))
    )
    (net (code "52") (name "Net-(3V3Reg-ADJ)") (class "Default")
      (node (ref "3V3Reg") (pin "1") (pinfunction "ADJ_1") (pintype "input"))
      (node (ref "R1") (pin "2") (pinfunction "2_2") (pintype "passive"))
      (node (ref "R2") (pin "1") (pinfunction "1_1") (pintype "passive"))
    )
    (net (code "53") (name "Net-(DRV1-PadEEP)") (class "Default")
      (node (ref "DRV1") (pin "EEP") (pinfunction "EEP_EEP") (pintype "passive"))
      (node (ref "STP1") (pin "1") (pinfunction "1_1") (pintype "passive"))
    )
    (net (code "54") (name "Net-(DRV1-PadOUT1)") (class "Default")
      (node (ref "DRV1") (pin "OUT1") (pinfunction "OUT1_OUT1") (pintype "passive"))
      (node (ref "STP1") (pin "2") (pinfunction "2_2") (pintype "passive"))
    )
    (net (code "55") (name "Net-(DRV1-PadOUT4)") (class "Default")
      (node (ref "DRV1") (pin "OUT4") (pinfunction "OUT4_OUT4") (pintype "passive"))
      (node (ref "STP1") (pin "5") (pinfunction "5_5") (pintype "passive"))
    )
    (net (code "56") (name "Net-(DRV2-PadEEP)") (class "Default")
      (node (ref "DRV2") (pin "EEP") (pinfunction "EEP_EEP") (pintype "passive"))
      (node (ref "STP2") (pin "1") (pinfunction "1_1") (pintype "passive"))
    )
    (net (code "57") (name "Net-(DRV2-PadOUT1)") (class "Default")
      (node (ref "DRV2") (pin "OUT1") (pinfunction "OUT1_OUT1") (pintype "passive"))
      (node (ref "STP2") (pin "2") (pinfunction "2_2") (pintype "passive"))
    )
    (net (code "58") (name "Net-(DRV2-PadOUT4)") (class "Default")
      (node (ref "DRV2") (pin "OUT4") (pinfunction "OUT4_OUT4") (pintype "passive"))
      (node (ref "STP2") (pin "5") (pinfunction "5_5") (pintype "passive"))
    )
    (net (code "59") (name "Net-(DRV3-PadEEP)") (class "Default")
      (node (ref "DRV3") (pin "EEP") (pinfunction "EEP_EEP") (pintype "passive"))
      (node (ref "STP3") (pin "1") (pinfunction "1_1") (pintype "passive"))
    )
    (net (code "60") (name "Net-(DRV3-PadOUT1)") (class "Default")
      (node (ref "DRV3") (pin "OUT1") (pinfunction "OUT1_OUT1") (pintype "passive"))
      (node (ref "STP3") (pin "2") (pinfunction "2_2") (pintype "passive"))
    )
    (net (code "61") (name "Net-(DRV3-PadOUT4)") (class "Default")
      (node (ref "DRV3") (pin "OUT4") (pinfunction "OUT4_OUT4") (pintype "passive"))
      (node (ref "STP3") (pin "5") (pinfunction "5_5") (pintype "passive"))
    )
    (net (code "62") (name "Net-(DRV4-PadEEP)") (class "Default")
      (node (ref "DRV4") (pin "EEP") (pinfunction "EEP_EEP") (pintype "passive"))
      (node (ref "STP4") (pin "1") (pinfunction "1_1") (pintype "passive"))
    )
    (net (code "63") (name "Net-(DRV4-PadOUT1)") (class "Default")
      (node (ref "DRV4") (pin "OUT1") (pinfunction "OUT1_OUT1") (pintype "passive"))
      (node (ref "STP4") (pin "2") (pinfunction "2_2") (pintype "passive"))
    )
    (net (code "64") (name "Net-(DRV4-PadOUT4)") (class "Default")
      (node (ref "DRV4") (pin "OUT4") (pinfunction "OUT4_OUT4") (pintype "passive"))
      (node (ref "STP4") (pin "5") (pinfunction "5_5") (pintype "passive"))
    )
    (net (code "65") (name "Net-(ESPHL-Pad15)") (class "Default")
      (node (ref "ESPHL") (pin "15") (pinfunction "15_15") (pintype "passive"))
      (node (ref "ESPHL") (pin "16") (pinfunction "16_16") (pintype "passive"))
    )
    (net (code "66") (name "Net-(ESPHL-Pad21)") (class "Default")
      (node (ref "ESPHL") (pin "21") (pinfunction "21_21") (pintype "passive"))
      (node (ref "ESPHL") (pin "22") (pinfunction "22_22") (pintype "passive"))
    )
    (net (code "67") (name "Net-(ESPHL-Pad23)") (class "Default")
      (node (ref "ESPHL") (pin "23") (pinfunction "23_23") (pintype "passive"))
      (node (ref "ESPHL") (pin "24") (pinfunction "24_24") (pintype "passive"))
    )
    (net (code "68") (name "Net-(ESPHL-Pad25)") (class "Default")
      (node (ref "ESPHL") (pin "25") (pinfunction "25_25") (pintype "passive"))
      (node (ref "ESPHL") (pin "26") (pinfunction "26_26") (pintype "passive"))
    )
    (net (code "69") (name "Net-(ESPHL-Pad27)") (class "Default")
      (node (ref "ESPHL") (pin "27") (pinfunction "27_27") (pintype "passive"))
      (node (ref "ESPHL") (pin "28") (pinfunction "28_28") (pintype "passive"))
    )
    (net (code "70") (name "Net-(ESPHL-Pad29)") (class "Default")
      (node (ref "ESPHL") (pin "29") (pinfunction "29_29") (pintype "passive"))
      (node (ref "ESPHL") (pin "30") (pinfunction "30_30") (pintype "passive"))
    )
    (net (code "71") (name "Net-(ESPHL-Pad31)") (class "Default")
      (node (ref "ESPHL") (pin "31") (pinfunction "31_31") (pintype "passive"))
      (node (ref "ESPHL") (pin "32") (pinfunction "32_32") (pintype "passive"))
    )
    (net (code "72") (name "Net-(ESPHL-Pad33)") (class "Default")
      (node (ref "ESPHL") (pin "33") (pinfunction "33_33") (pintype "passive"))
      (node (ref "ESPHL") (pin "34") (pinfunction "34_34") (pintype "passive"))
    )
    (net (code "73") (name "Net-(ESPHL-Pad35)") (class "Default")
      (node (ref "ESPHL") (pin "35") (pinfunction "35_35") (pintype "passive"))
      (node (ref "ESPHL") (pin "36") (pinfunction "36_36") (pintype "passive"))
    )
    (net (code "74") (name "Net-(ESPHL-Pad37)") (class "Default")
      (node (ref "ESPHL") (pin "37") (pinfunction "37_37") (pintype "passive"))
      (node (ref "ESPHL") (pin "38") (pinfunction "38_38") (pintype "passive"))
    )
    (net (code "75") (name "Net-(ESPHL-Pad39)") (class "Default")
      (node (ref "ESPHL") (pin "39") (pinfunction "39_39") (pintype "passive"))
      (node (ref "ESPHL") (pin "40") (pinfunction "40_40") (pintype "passive"))
    )
    (net (code "76") (name "Net-(ESPHR-Pad1)") (class "Default")
      (node (ref "ESPHR") (pin "1") (pinfunction "1_1") (pintype "passive"))
      (node (ref "ESPHR") (pin "2") (pinfunction "2_2") (pintype "passive"))
    )
    (net (code "77") (name "Net-(ESPHR-Pad5)") (class "Default")
      (node (ref "ESPHR") (pin "5") (pinfunction "5_5") (pintype "passive"))
      (node (ref "ESPHR") (pin "6") (pinfunction "6_6") (pintype "passive"))
    )
    (net (code "78") (name "Net-(ESPHR-Pad7)") (class "Default")
      (node (ref "ESPHR") (pin "7") (pinfunction "7_7") (pintype "passive"))
      (node (ref "ESPHR") (pin "8") (pinfunction "8_8") (pintype "passive"))
    )
    (net (code "79") (name "Net-(ESPHR-Pad10)") (class "Default")
      (node (ref "ESPHR") (pin "10") (pinfunction "10_10") (pintype "passive"))
      (node (ref "ESPHR") (pin "9") (pinfunction "9_9") (pintype "passive"))
    )
    (net (code "80") (name "Net-(ESPHR-Pad11)") (class "Default")
      (node (ref "ESPHR") (pin "11") (pinfunction "11_11") (pintype "passive"))
      (node (ref "ESPHR") (pin "12") (pinfunction "12_12") (pintype "passive"))
    )
    (net (code "81") (name "Net-(ESPHR-Pad15)") (class "Default")
      (node (ref "ESPHR") (pin "15") (pinfunction "15_15") (pintype "passive"))
      (node (ref "ESPHR") (pin "16") (pinfunction "16_16") (pintype "passive"))
    )
    (net (code "82") (name "Net-(ESPHR-Pad21)") (class "Default")
      (node (ref "ESPHR") (pin "21") (pinfunction "21_21") (pintype "passive"))
      (node (ref "ESPHR") (pin "22") (pinfunction "22_22") (pintype "passive"))
    )
    (net (code "83") (name "Net-(ESPHR-Pad25)") (class "Default")
      (node (ref "ESPHR") (pin "25") (pinfunction "25_25") (pintype "passive"))
      (node (ref "ESPHR") (pin "26") (pinfunction "26_26") (pintype "passive"))
    )
    (net (code "84") (name "Net-(ESPHR-Pad33)") (class "Default")
      (node (ref "ESPHR") (pin "33") (pinfunction "33_33") (pintype "passive"))
      (node (ref "ESPHR") (pin "34") (pinfunction "34_34") (pintype "passive"))
    )
    (net (code "85") (name "Net-(ESPHR-Pad35)") (class "Default")
      (node (ref "ESPHR") (pin "35") (pinfunction "35_35") (pintype "passive"))
      (node (ref "ESPHR") (pin "36") (pinfunction "36_36") (pintype "passive"))
    )
    (net (code "86") (name "Net-(ESPHR-Pad37)") (class "Default")
      (node (ref "ESPHR") (pin "37") (pinfunction "37_37") (pintype "passive"))
      (node (ref "ESPHR") (pin "38") (pinfunction "38_38") (pintype "passive"))
    )
    (net (code "87") (name "Net-(ESPHR-Pad39)") (class "Default")
      (node (ref "ESPHR") (pin "39") (pinfunction "39_39") (pintype "passive"))
      (node (ref "ESPHR") (pin "40") (pinfunction "40_40") (pintype "passive"))
    )
    (net (code "88") (name "Net-(PIHL-Pad1)") (class "Default")
      (node (ref "PIHL") (pin "1") (pinfunction "1_1") (pintype "passive"))
      (node (ref "PIHL") (pin "2") (pinfunction "2_2") (pintype "passive"))
    )
    (net (code "89") (name "Net-(PIHL-Pad7)") (class "Default")
      (node (ref "PIHL") (pin "7") (pinfunction "7_7") (pintype "passive"))
      (node (ref "PIHL") (pin "8") (pinfunction "8_8") (pintype "passive"))
    )
    (net (code "90") (name "Net-(PIHL-Pad10)") (class "Default")
      (node (ref "PIHL") (pin "10") (pinfunction "10_10") (pintype "passive"))
      (node (ref "PIHL") (pin "9") (pinfunction "9_9") (pintype "passive"))
    )
    (net (code "91") (name "Net-(PIHL-Pad11)") (class "Default")
      (node (ref "PIHL") (pin "11") (pinfunction "11_11") (pintype "passive"))
      (node (ref "PIHL") (pin "12") (pinfunction "12_12") (pintype "passive"))
    )
    (net (code "92") (name "Net-(PIHL-Pad15)") (class "Default")
      (node (ref "PIHL") (pin "15") (pinfunction "15_15") (pintype "passive"))
      (node (ref "PIHL") (pin "16") (pinfunction "16_16") (pintype "passive"))
    )
    (net (code "93") (name "Net-(PIHL-Pad21)") (class "Default")
      (node (ref "PIHL") (pin "21") (pinfunction "21_21") (pintype "passive"))
      (node (ref "PIHL") (pin "22") (pinfunction "22_22") (pintype "passive"))
    )
    (net (code "94") (name "Net-(PIHL-Pad25)") (class "Default")
      (node (ref "PIHL") (pin "25") (pinfunction "25_25") (pintype "passive"))
      (node (ref "PIHL") (pin "26") (pinfunction "26_26") (pintype "passive"))
    )
    (net (code "95") (name "Net-(PIHL-Pad35)") (class "Default")
      (node (ref "PIHL") (pin "35") (pinfunction "35_35") (pintype "passive"))
      (node (ref "PIHL") (pin "36") (pinfunction "36_36") (pintype "passive"))
    )
    (net (code "96") (name "Net-(PIHR-Pad5)") (class "Default")
      (node (ref "PIHR") (pin "5") (pinfunction "5_5") (pintype "passive"))
      (node (ref "PIHR") (pin "6") (pinfunction "6_6") (pintype "passive"))
    )
    (net (code "97") (name "Net-(PIHR-Pad15)") (class "Default")
      (node (ref "PIHR") (pin "15") (pinfunction "15_15") (pintype "passive"))
      (node (ref "PIHR") (pin "16") (pinfunction "16_16") (pintype "passive"))
    )
    (net (code "98") (name "Net-(PIHR-Pad25)") (class "Default")
      (node (ref "PIHR") (pin "25") (pinfunction "25_25") (pintype "passive"))
      (node (ref "PIHR") (pin "26") (pinfunction "26_26") (pintype "passive"))
    )
    (net (code "99") (name "Net-(PIHR-Pad35)") (class "Default")
      (node (ref "PIHR") (pin "35") (pinfunction "35_35") (pintype "passive"))
      (node (ref "PIHR") (pin "36") (pinfunction "36_36") (pintype "passive"))
    )
    (net (code "100") (name "Net-(PIM1-Pad1)") (class "Default")
      (node (ref "PIM1") (pin "1") (pinfunction "1_1") (pintype "passive"))
      (node (ref "R1k_1") (pin "2") (pinfunction "2_2") (pintype "passive"))
    )
    (net (code "101") (name "Net-(PIM2-Pad1)") (class "Default")
      (node (ref "PIM2") (pin "1") (pinfunction "1_1") (pintype "passive"))
      (node (ref "R1k_2") (pin "2") (pinfunction "2_2") (pintype "passive"))
    )
    (net (code "102") (name "Net-(PIM3-Pad1)") (class "Default")
      (node (ref "PIM3") (pin "1") (pinfunction "1_1") (pintype "passive"))
      (node (ref "R1k_3") (pin "2") (pinfunction "2_2") (pintype "passive"))
    )
    (net (code "103") (name "Net-(PIM4-Pad1)") (class "Default")
      (node (ref "PIM4") (pin "1") (pinfunction "1_1") (pintype "passive"))
      (node (ref "R1k_4") (pin "2") (pinfunction "2_2") (pintype "passive"))
    )
    (net (code "104") (name "unconnected-(AudioModule-Pad4)") (class "Default")
      (node (ref "AudioModule") (pin "4") (pinfunction "4_4") (pintype "passive+no_connect"))
    )
    (net (code "105") (name "unconnected-(AudioModule-Pad5)") (class "Default")
      (node (ref "AudioModule") (pin "5") (pinfunction "5_5") (pintype "passive+no_connect"))
    )
    (net (code "106") (name "unconnected-(DRV1-PadULT)") (class "Default")
      (node (ref "DRV1") (pin "ULT") (pinfunction "ULT_ULT") (pintype "passive+no_connect"))
    )
    (net (code "107") (name "unconnected-(DRV2-PadULT)") (class "Default")
      (node (ref "DRV2") (pin "ULT") (pinfunction "ULT_ULT") (pintype "passive+no_connect"))
    )
    (net (code "108") (name "unconnected-(DRV3-PadULT)") (class "Default")
      (node (ref "DRV3") (pin "ULT") (pinfunction "ULT_ULT") (pintype "passive+no_connect"))
    )
    (net (code "109") (name "unconnected-(DRV4-PadULT)") (class "Default")
      (node (ref "DRV4") (pin "ULT") (pinfunction "ULT_ULT") (pintype "passive+no_connect"))
    )
    (net (code "110") (name "unconnected-(LCD_Header-Pad9)") (class "Default")
      (node (ref "LCD_Header") (pin "9") (pinfunction "9_9") (pintype "passive+no_connect"))
    )
    (net (code "111") (name "unconnected-(PIM1-Pad2)") (class "Default")
      (node (ref "PIM1") (pin "2") (pinfunction "2_2") (pintype "passive+no_connect"))
    )
    (net (code "112") (name "unconnected-(PIM2-Pad2)") (class "Default")
      (node (ref "PIM2") (pin "2") (pinfunction "2_2") (pintype "passive+no_connect"))
    )
    (net (code "113") (name "unconnected-(PIM3-Pad2)") (class "Default")
      (node (ref "PIM3") (pin "2") (pinfunction "2_2") (pintype "passive+no_connect"))
    )
    (net (code "114") (name "unconnected-(PIM4-Pad2)") (class "Default")
      (node (ref "PIM4") (pin "2") (pinfunction "2_2") (pintype "passive+no_connect"))
    )
    (net (code "115") (name "unconnected-(RPI Pico2-3V3-Pad36)") (class "Default")
      (node (ref "RPI Pico2") (pin "36") (pinfunction "3V3_36") (pintype "power_in"))
    )
    (net (code "116") (name "unconnected-(RPI Pico2-AVREF-Pad35)") (class "Default")
      (node (ref "RPI Pico2") (pin "35") (pinfunction "AVREF_35") (pintype "power_in"))
    )
    (net (code "117") (name "unconnected-(RPI Pico2-EN-Pad37)") (class "Default")
      (node (ref "RPI Pico2") (pin "37") (pinfunction "EN_37") (pintype "input"))
    )
    (net (code "118") (name "unconnected-(RPI Pico2-GND-Pad3)") (class "Default")
      (node (ref "RPI Pico2") (pin "3") (pinfunction "GND_3") (pintype "power_in"))
    )
    (net (code "119") (name "unconnected-(RPI Pico2-GND-Pad8)") (class "Default")
      (node (ref "RPI Pico2") (pin "8") (pinfunction "GND_8") (pintype "power_in"))
    )
    (net (code "120") (name "unconnected-(RPI Pico2-GND-Pad13)") (class "Default")
      (node (ref "RPI Pico2") (pin "13") (pinfunction "GND_13") (pintype "power_in"))
    )
    (net (code "121") (name "unconnected-(RPI Pico2-GND-Pad18)") (class "Default")
      (node (ref "RPI Pico2") (pin "18") (pinfunction "GND_18") (pintype "power_in"))
    )
    (net (code "122") (name "unconnected-(RPI Pico2-GND-Pad23)") (class "Default")
      (node (ref "RPI Pico2") (pin "23") (pinfunction "GND_23") (pintype "power_in"))
    )
    (net (code "123") (name "unconnected-(RPI Pico2-GND-Pad28)") (class "Default")
      (node (ref "RPI Pico2") (pin "28") (pinfunction "GND_28") (pintype "power_in"))
    )
    (net (code "124") (name "unconnected-(RPI Pico2-GND-Pad33)") (class "Default")
      (node (ref "RPI Pico2") (pin "33") (pinfunction "GND_33") (pintype "power_in"))
    )
    (net (code "125") (name "unconnected-(RPI Pico2-GND-Pad38)") (class "Default")
      (node (ref "RPI Pico2") (pin "38") (pinfunction "GND_38") (pintype "power_in"))
    )
    (net (code "126") (name "unconnected-(RPI Pico2-GND-Pad42)") (class "Default")
      (node (ref "RPI Pico2") (pin "42") (pinfunction "GND_42") (pintype "power_in"))
    )
    (net (code "127") (name "unconnected-(RPI Pico2-GP0-Pad1)") (class "Default")
      (node (ref "RPI Pico2") (pin "1") (pinfunction "GP0_1") (pintype "bidirectional"))
    )
    (net (code "128") (name "unconnected-(RPI Pico2-GP1-Pad2)") (class "Default")
      (node (ref "RPI Pico2") (pin "2") (pinfunction "GP1_2") (pintype "bidirectional"))
    )
    (net (code "129") (name "unconnected-(RPI Pico2-GP2-Pad4)") (class "Default")
      (node (ref "RPI Pico2") (pin "4") (pinfunction "GP2_4") (pintype "bidirectional"))
    )
    (net (code "130") (name "unconnected-(RPI Pico2-GP3-Pad5)") (class "Default")
      (node (ref "RPI Pico2") (pin "5") (pinfunction "GP3_5") (pintype "bidirectional"))
    )
    (net (code "131") (name "unconnected-(RPI Pico2-GP4-Pad6)") (class "Default")
      (node (ref "RPI Pico2") (pin "6") (pinfunction "GP4_6") (pintype "bidirectional"))
    )
    (net (code "132") (name "unconnected-(RPI Pico2-GP5-Pad7)") (class "Default")
      (node (ref "RPI Pico2") (pin "7") (pinfunction "GP5_7") (pintype "bidirectional"))
    )
    (net (code "133") (name "unconnected-(RPI Pico2-GP6-Pad9)") (class "Default")
      (node (ref "RPI Pico2") (pin "9") (pinfunction "GP6_9") (pintype "bidirectional"))
    )
    (net (code "134") (name "unconnected-(RPI Pico2-GP7-Pad10)") (class "Default")
      (node (ref "RPI Pico2") (pin "10") (pinfunction "GP7_10") (pintype "bidirectional"))
    )
    (net (code "135") (name "unconnected-(RPI Pico2-GP8-Pad11)") (class "Default")
      (node (ref "RPI Pico2") (pin "11") (pinfunction "GP8_11") (pintype "bidirectional"))
    )
    (net (code "136") (name "unconnected-(RPI Pico2-GP9-Pad12)") (class "Default")
      (node (ref "RPI Pico2") (pin "12") (pinfunction "GP9_12") (pintype "bidirectional"))
    )
    (net (code "137") (name "unconnected-(RPI Pico2-GP10-Pad14)") (class "Default")
      (node (ref "RPI Pico2") (pin "14") (pinfunction "GP10_14") (pintype "bidirectional"))
    )
    (net (code "138") (name "unconnected-(RPI Pico2-GP11-Pad15)") (class "Default")
      (node (ref "RPI Pico2") (pin "15") (pinfunction "GP11_15") (pintype "bidirectional"))
    )
    (net (code "139") (name "unconnected-(RPI Pico2-GP12-Pad16)") (class "Default")
      (node (ref "RPI Pico2") (pin "16") (pinfunction "GP12_16") (pintype "bidirectional"))
    )
    (net (code "140") (name "unconnected-(RPI Pico2-GP13-Pad17)") (class "Default")
      (node (ref "RPI Pico2") (pin "17") (pinfunction "GP13_17") (pintype "bidirectional"))
    )
    (net (code "141") (name "unconnected-(RPI Pico2-GP14-Pad19)") (class "Default")
      (node (ref "RPI Pico2") (pin "19") (pinfunction "GP14_19") (pintype "bidirectional"))
    )
    (net (code "142") (name "unconnected-(RPI Pico2-GP15-Pad20)") (class "Default")
      (node (ref "RPI Pico2") (pin "20") (pinfunction "GP15_20") (pintype "bidirectional"))
    )
    (net (code "143") (name "unconnected-(RPI Pico2-GP16-Pad21)") (class "Default")
      (node (ref "RPI Pico2") (pin "21") (pinfunction "GP16_21") (pintype "bidirectional"))
    )
    (net (code "144") (name "unconnected-(RPI Pico2-GP17-Pad22)") (class "Default")
      (node (ref "RPI Pico2") (pin "22") (pinfunction "GP17_22") (pintype "bidirectional"))
    )
    (net (code "145") (name "unconnected-(RPI Pico2-GP18-Pad24)") (class "Default")
      (node (ref "RPI Pico2") (pin "24") (pinfunction "GP18_24") (pintype "bidirectional"))
    )
    (net (code "146") (name "unconnected-(RPI Pico2-GP19-Pad25)") (class "Default")
      (node (ref "RPI Pico2") (pin "25") (pinfunction "GP19_25") (pintype "bidirectional"))
    )
    (net (code "147") (name "unconnected-(RPI Pico2-GP20-Pad26)") (class "Default")
      (node (ref "RPI Pico2") (pin "26") (pinfunction "GP20_26") (pintype "bidirectional"))
    )
    (net (code "148") (name "unconnected-(RPI Pico2-GP21-Pad27)") (class "Default")
      (node (ref "RPI Pico2") (pin "27") (pinfunction "GP21_27") (pintype "bidirectional"))
    )
    (net (code "149") (name "unconnected-(RPI Pico2-GP22-Pad29)") (class "Default")
      (node (ref "RPI Pico2") (pin "29") (pinfunction "GP22_29") (pintype "bidirectional"))
    )
    (net (code "150") (name "unconnected-(RPI Pico2-GP26-Pad31)") (class "Default")
      (node (ref "RPI Pico2") (pin "31") (pinfunction "GP26_31") (pintype "bidirectional"))
    )
    (net (code "151") (name "unconnected-(RPI Pico2-GP27-Pad32)") (class "Default")
      (node (ref "RPI Pico2") (pin "32") (pinfunction "GP27_32") (pintype "bidirectional"))
    )
    (net (code "152") (name "unconnected-(RPI Pico2-GP28-Pad34)") (class "Default")
      (node (ref "RPI Pico2") (pin "34") (pinfunction "GP28_34") (pintype "bidirectional"))
    )
    (net (code "153") (name "unconnected-(RPI Pico2-RUN-Pad30)") (class "Default")
      (node (ref "RPI Pico2") (pin "30") (pinfunction "RUN_30") (pintype "input"))
    )
    (net (code "154") (name "unconnected-(RPI Pico2-SWCLK-Pad41)") (class "Default")
      (node (ref "RPI Pico2") (pin "41") (pinfunction "SWCLK_41") (pintype "bidirectional"))
    )
    (net (code "155") (name "unconnected-(RPI Pico2-SWDIO-Pad43)") (class "Default")
      (node (ref "RPI Pico2") (pin "43") (pinfunction "SWDIO_43") (pintype "bidirectional"))
    )
    (net (code "156") (name "unconnected-(RPI Pico2-VBUS-Pad40)") (class "Default")
      (node (ref "RPI Pico2") (pin "40") (pinfunction "VBUS_40") (pintype "power_in"))
    )
    (net (code "157") (name "unconnected-(RPI Pico2-VSYS-Pad39)") (class "Default")
      (node (ref "RPI Pico2") (pin "39") (pinfunction "VSYS_39") (pintype "power_in"))
    )
  )
)
